# Communication_Board_Rev_A.net
KiCad netlist of a schematic drawn in EAGLE
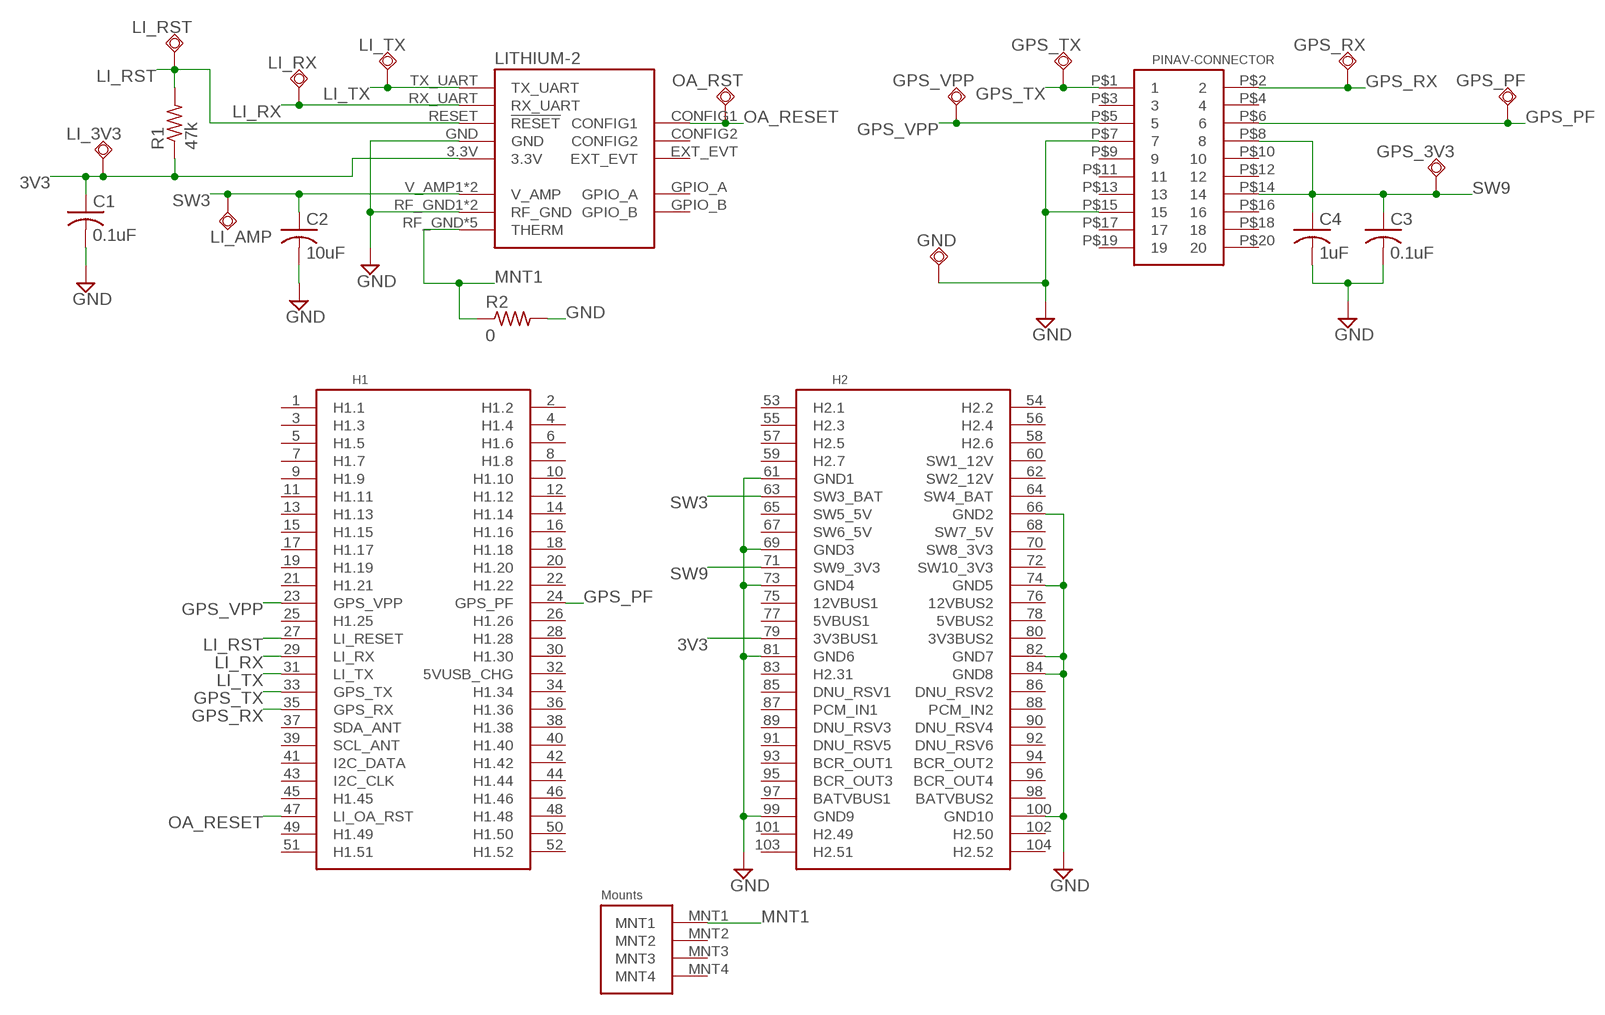
[diagram p0: schematic, sheet 1]

(export (version "E")
  (design (tool "Eeschema 10.0.6"))
  (components
    (comp (ref "C1")
      (value "0.1uF")
      (footprint "eagle-import:C0805")
      (libsource (lib "eagle-import") (part "C-USC0805"))
    )
    (comp (ref "C2")
      (value "10uF")
      (footprint "eagle-import:C0805")
      (libsource (lib "eagle-import") (part "C-USC0805"))
    )
    (comp (ref "C3")
      (value "0.1uF")
      (footprint "eagle-import:C0805")
      (libsource (lib "eagle-import") (part "C-USC0805"))
    )
    (comp (ref "C4")
      (value "1uF")
      (footprint "eagle-import:C0805")
      (libsource (lib "eagle-import") (part "C-USC0805"))
    )
    (comp (ref "GND")
      (value "TPSQTP10SQ")
      (footprint "eagle-import:TP10SQ")
      (libsource (lib "eagle-import") (part "TPSQTP10SQ"))
    )
    (comp (ref "GPS_3V3")
      (value "TPSQTP10SQ")
      (footprint "eagle-import:TP10SQ")
      (libsource (lib "eagle-import") (part "TPSQTP10SQ"))
    )
    (comp (ref "GPS_PF")
      (value "TPSQTP10SQ")
      (footprint "eagle-import:TP10SQ")
      (libsource (lib "eagle-import") (part "TPSQTP10SQ"))
    )
    (comp (ref "GPS_RX")
      (value "TPSQTP10SQ")
      (footprint "eagle-import:TP10SQ")
      (libsource (lib "eagle-import") (part "TPSQTP10SQ"))
    )
    (comp (ref "GPS_TX")
      (value "TPSQTP10SQ")
      (footprint "eagle-import:TP10SQ")
      (libsource (lib "eagle-import") (part "TPSQTP10SQ"))
    )
    (comp (ref "GPS_VPP")
      (value "TPSQTP10SQ")
      (footprint "eagle-import:TP10SQ")
      (libsource (lib "eagle-import") (part "TPSQTP10SQ"))
    )
    (comp (ref "LITHIUM-2")
      (value "LI-2")
      (footprint "eagle-import:LI-2")
      (libsource (lib "eagle-import") (part "LI-2"))
    )
    (comp (ref "LI_3V3")
      (value "TPSQTP10SQ")
      (footprint "eagle-import:TP10SQ")
      (libsource (lib "eagle-import") (part "TPSQTP10SQ"))
    )
    (comp (ref "LI_AMP")
      (value "TPSQTP10SQ")
      (footprint "eagle-import:TP10SQ")
      (libsource (lib "eagle-import") (part "TPSQTP10SQ"))
    )
    (comp (ref "LI_RST")
      (value "TPSQTP10SQ")
      (footprint "eagle-import:TP10SQ")
      (libsource (lib "eagle-import") (part "TPSQTP10SQ"))
    )
    (comp (ref "LI_RX")
      (value "TPSQTP10SQ")
      (footprint "eagle-import:TP10SQ")
      (libsource (lib "eagle-import") (part "TPSQTP10SQ"))
    )
    (comp (ref "LI_TX")
      (value "TPSQTP10SQ")
      (footprint "eagle-import:TP10SQ")
      (libsource (lib "eagle-import") (part "TPSQTP10SQ"))
    )
    (comp (ref "OA_RST")
      (value "TPSQTP10SQ")
      (footprint "eagle-import:TP10SQ")
      (libsource (lib "eagle-import") (part "TPSQTP10SQ"))
    )
    (comp (ref "PINAV-CONNECTOR")
      (value "HLE-110-02-X-DVHLE-110-X-DV-PE-BA")
      (footprint "eagle-import:HLE-110-02-X-DV-PE-BE")
      (libsource (lib "eagle-import") (part "HLE-110-02-X-DVHLE-110-X-DV-PE-BA"))
    )
    (comp (ref "R1")
      (value "47k")
      (footprint "eagle-import:R0805")
      (libsource (lib "eagle-import") (part "R-US_R0805"))
    )
    (comp (ref "R2")
      (value "0")
      (footprint "eagle-import:R0805")
      (libsource (lib "eagle-import") (part "R-US_R0805"))
    )
    (comp (ref "U$1")
      (value "PC104_NO_DIMENSION")
      (footprint "eagle-import:PC104_NO_DIMENSION")
      (libsource (lib "eagle-import") (part "PC104_NO_DIMENSION"))
    )
  )
  (nets
    (net (code "1") (name "/3V3") (class "Default")
      (node (ref "C1") (pin "1") (pinfunction "1_1") (pintype "passive"))
      (node (ref "LITHIUM-2") (pin "3.3V") (pinfunction "3.3V_3.3V") (pintype "power_in"))
      (node (ref "LI_3V3") (pin "TP") (pinfunction "TP_TP") (pintype "input"))
      (node (ref "R1") (pin "1") (pinfunction "1_1") (pintype "passive"))
      (node (ref "U$1") (pin "79") (pinfunction "3V3BUS1_79") (pintype "bidirectional"))
    )
    (net (code "2") (name "/GPS_PF") (class "Default")
      (node (ref "GPS_PF") (pin "TP") (pinfunction "TP_TP") (pintype "input"))
      (node (ref "PINAV-CONNECTOR") (pin "P$6") (pinfunction "6_P$6") (pintype "bidirectional"))
      (node (ref "U$1") (pin "24") (pinfunction "GPS_PF_24") (pintype "bidirectional"))
    )
    (net (code "3") (name "/GPS_RX") (class "Default")
      (node (ref "GPS_RX") (pin "TP") (pinfunction "TP_TP") (pintype "input"))
      (node (ref "PINAV-CONNECTOR") (pin "P$2") (pinfunction "2_P$2") (pintype "bidirectional"))
      (node (ref "U$1") (pin "35") (pinfunction "GPS_RX_35") (pintype "bidirectional"))
    )
    (net (code "4") (name "/GPS_TX") (class "Default")
      (node (ref "GPS_TX") (pin "TP") (pinfunction "TP_TP") (pintype "input"))
      (node (ref "PINAV-CONNECTOR") (pin "P$1") (pinfunction "1_P$1") (pintype "bidirectional"))
      (node (ref "U$1") (pin "33") (pinfunction "GPS_TX_33") (pintype "bidirectional"))
    )
    (net (code "5") (name "/GPS_VPP") (class "Default")
      (node (ref "GPS_VPP") (pin "TP") (pinfunction "TP_TP") (pintype "input"))
      (node (ref "PINAV-CONNECTOR") (pin "P$5") (pinfunction "5_P$5") (pintype "bidirectional"))
      (node (ref "U$1") (pin "23") (pinfunction "GPS_VPP_23") (pintype "bidirectional"))
    )
    (net (code "6") (name "/LI_RST") (class "Default")
      (node (ref "LITHIUM-2") (pin "RESET") (pinfunction "~{RESET}_RESET") (pintype "input"))
      (node (ref "LI_RST") (pin "TP") (pinfunction "TP_TP") (pintype "input"))
      (node (ref "R1") (pin "2") (pinfunction "2_2") (pintype "passive"))
      (node (ref "U$1") (pin "27") (pinfunction "LI_RESET_27") (pintype "bidirectional"))
    )
    (net (code "7") (name "/LI_RX") (class "Default")
      (node (ref "LITHIUM-2") (pin "RX_UART") (pinfunction "RX_UART_RX_UART") (pintype "input"))
      (node (ref "LI_RX") (pin "TP") (pinfunction "TP_TP") (pintype "input"))
      (node (ref "U$1") (pin "29") (pinfunction "LI_RX_29") (pintype "bidirectional"))
    )
    (net (code "8") (name "/LI_TX") (class "Default")
      (node (ref "LITHIUM-2") (pin "TX_UART") (pinfunction "TX_UART_TX_UART") (pintype "output"))
      (node (ref "LI_TX") (pin "TP") (pinfunction "TP_TP") (pintype "input"))
      (node (ref "U$1") (pin "31") (pinfunction "LI_TX_31") (pintype "bidirectional"))
    )
    (net (code "9") (name "/MNT1") (class "Default")
      (node (ref "LITHIUM-2") (pin "RF_GND") (pinfunction "THERM_RF_GND") (pintype "passive"))
      (node (ref "LITHIUM-2") (pin "THERM1") (pinfunction "THERM_THERM1") (pintype "passive"))
      (node (ref "LITHIUM-2") (pin "THERM2") (pinfunction "THERM_THERM2") (pintype "passive"))
      (node (ref "LITHIUM-2") (pin "THERM3") (pinfunction "THERM_THERM3") (pintype "passive"))
      (node (ref "LITHIUM-2") (pin "THERM4") (pinfunction "THERM_THERM4") (pintype "passive"))
      (node (ref "R2") (pin "1") (pinfunction "1_1") (pintype "passive"))
      (node (ref "U$1") (pin "MNT1") (pinfunction "MNT1_MNT1") (pintype "passive"))
    )
    (net (code "10") (name "/OA_RESET") (class "Default")
      (node (ref "LITHIUM-2") (pin "CONFIG1") (pinfunction "CONFIG1_CONFIG1") (pintype "bidirectional"))
      (node (ref "OA_RST") (pin "TP") (pinfunction "TP_TP") (pintype "input"))
      (node (ref "U$1") (pin "47") (pinfunction "LI_OA_RST_47") (pintype "bidirectional"))
    )
    (net (code "11") (name "/SW3") (class "Default")
      (node (ref "C2") (pin "1") (pinfunction "1_1") (pintype "passive"))
      (node (ref "LITHIUM-2") (pin "V_AMP1") (pinfunction "V_AMP_V_AMP1") (pintype "power_in"))
      (node (ref "LITHIUM-2") (pin "V_AMP2") (pinfunction "V_AMP_V_AMP2") (pintype "power_in"))
      (node (ref "LI_AMP") (pin "TP") (pinfunction "TP_TP") (pintype "input"))
      (node (ref "U$1") (pin "63") (pinfunction "SW3_BAT_63") (pintype "bidirectional"))
    )
    (net (code "12") (name "/SW9") (class "Default")
      (node (ref "C3") (pin "1") (pinfunction "1_1") (pintype "passive"))
      (node (ref "C4") (pin "1") (pinfunction "1_1") (pintype "passive"))
      (node (ref "GPS_3V3") (pin "TP") (pinfunction "TP_TP") (pintype "input"))
      (node (ref "PINAV-CONNECTOR") (pin "P$14") (pinfunction "14_P$14") (pintype "bidirectional"))
      (node (ref "PINAV-CONNECTOR") (pin "P$8") (pinfunction "8_P$8") (pintype "bidirectional"))
      (node (ref "U$1") (pin "71") (pinfunction "SW9_3V3_71") (pintype "bidirectional"))
    )
    (net (code "13") (name "GND") (class "Default")
      (node (ref "C1") (pin "2") (pinfunction "2_2") (pintype "passive"))
      (node (ref "C2") (pin "2") (pinfunction "2_2") (pintype "passive"))
      (node (ref "C3") (pin "2") (pinfunction "2_2") (pintype "passive"))
      (node (ref "C4") (pin "2") (pinfunction "2_2") (pintype "passive"))
      (node (ref "GND") (pin "TP") (pinfunction "TP_TP") (pintype "input"))
      (node (ref "LITHIUM-2") (pin "GND") (pinfunction "GND_GND") (pintype "power_in"))
      (node (ref "LITHIUM-2") (pin "RF_GND1") (pinfunction "RF_GND_RF_GND1") (pintype "power_in"))
      (node (ref "LITHIUM-2") (pin "RF_GND2") (pinfunction "RF_GND_RF_GND2") (pintype "power_in"))
      (node (ref "PINAV-CONNECTOR") (pin "P$15") (pinfunction "15_P$15") (pintype "bidirectional"))
      (node (ref "PINAV-CONNECTOR") (pin "P$7") (pinfunction "7_P$7") (pintype "bidirectional"))
      (node (ref "R2") (pin "2") (pinfunction "2_2") (pintype "passive"))
      (node (ref "U$1") (pin "100") (pinfunction "GND10_100") (pintype "bidirectional"))
      (node (ref "U$1") (pin "61") (pinfunction "GND1_61") (pintype "bidirectional"))
      (node (ref "U$1") (pin "66") (pinfunction "GND2_66") (pintype "bidirectional"))
      (node (ref "U$1") (pin "69") (pinfunction "GND3_69") (pintype "bidirectional"))
      (node (ref "U$1") (pin "73") (pinfunction "GND4_73") (pintype "bidirectional"))
      (node (ref "U$1") (pin "74") (pinfunction "GND5_74") (pintype "bidirectional"))
      (node (ref "U$1") (pin "81") (pinfunction "GND6_81") (pintype "bidirectional"))
      (node (ref "U$1") (pin "82") (pinfunction "GND7_82") (pintype "bidirectional"))
      (node (ref "U$1") (pin "84") (pinfunction "GND8_84") (pintype "bidirectional"))
      (node (ref "U$1") (pin "99") (pinfunction "GND9_99") (pintype "bidirectional"))
    )
    (net (code "14") (name "unconnected-(LITHIUM-2-PadCONFIG2)") (class "Default")
      (node (ref "LITHIUM-2") (pin "CONFIG2") (pinfunction "CONFIG2_CONFIG2") (pintype "bidirectional"))
    )
    (net (code "15") (name "unconnected-(LITHIUM-2-PadEXT_EVT)") (class "Default")
      (node (ref "LITHIUM-2") (pin "EXT_EVT") (pinfunction "EXT_EVT_EXT_EVT") (pintype "bidirectional"))
    )
    (net (code "16") (name "unconnected-(LITHIUM-2-PadGPIO_A)") (class "Default")
      (node (ref "LITHIUM-2") (pin "GPIO_A") (pinfunction "GPIO_A_GPIO_A") (pintype "bidirectional"))
    )
    (net (code "17") (name "unconnected-(LITHIUM-2-PadGPIO_B)") (class "Default")
      (node (ref "LITHIUM-2") (pin "GPIO_B") (pinfunction "GPIO_B_GPIO_B") (pintype "bidirectional"))
    )
    (net (code "18") (name "unconnected-(PINAV-CONNECTOR-3-PadP$3)") (class "Default")
      (node (ref "PINAV-CONNECTOR") (pin "P$3") (pinfunction "3_P$3") (pintype "bidirectional"))
    )
    (net (code "19") (name "unconnected-(PINAV-CONNECTOR-4-PadP$4)") (class "Default")
      (node (ref "PINAV-CONNECTOR") (pin "P$4") (pinfunction "4_P$4") (pintype "bidirectional"))
    )
    (net (code "20") (name "unconnected-(PINAV-CONNECTOR-9-PadP$9)") (class "Default")
      (node (ref "PINAV-CONNECTOR") (pin "P$9") (pinfunction "9_P$9") (pintype "bidirectional"))
    )
    (net (code "21") (name "unconnected-(PINAV-CONNECTOR-10-PadP$10)") (class "Default")
      (node (ref "PINAV-CONNECTOR") (pin "P$10") (pinfunction "10_P$10") (pintype "bidirectional"))
    )
    (net (code "22") (name "unconnected-(PINAV-CONNECTOR-11-PadP$11)") (class "Default")
      (node (ref "PINAV-CONNECTOR") (pin "P$11") (pinfunction "11_P$11") (pintype "bidirectional"))
    )
    (net (code "23") (name "unconnected-(PINAV-CONNECTOR-12-PadP$12)") (class "Default")
      (node (ref "PINAV-CONNECTOR") (pin "P$12") (pinfunction "12_P$12") (pintype "bidirectional"))
    )
    (net (code "24") (name "unconnected-(PINAV-CONNECTOR-13-PadP$13)") (class "Default")
      (node (ref "PINAV-CONNECTOR") (pin "P$13") (pinfunction "13_P$13") (pintype "bidirectional"))
    )
    (net (code "25") (name "unconnected-(PINAV-CONNECTOR-16-PadP$16)") (class "Default")
      (node (ref "PINAV-CONNECTOR") (pin "P$16") (pinfunction "16_P$16") (pintype "bidirectional"))
    )
    (net (code "26") (name "unconnected-(PINAV-CONNECTOR-17-PadP$17)") (class "Default")
      (node (ref "PINAV-CONNECTOR") (pin "P$17") (pinfunction "17_P$17") (pintype "bidirectional"))
    )
    (net (code "27") (name "unconnected-(PINAV-CONNECTOR-18-PadP$18)") (class "Default")
      (node (ref "PINAV-CONNECTOR") (pin "P$18") (pinfunction "18_P$18") (pintype "bidirectional"))
    )
    (net (code "28") (name "unconnected-(PINAV-CONNECTOR-19-PadP$19)") (class "Default")
      (node (ref "PINAV-CONNECTOR") (pin "P$19") (pinfunction "19_P$19") (pintype "bidirectional"))
    )
    (net (code "29") (name "unconnected-(PINAV-CONNECTOR-20-PadP$20)") (class "Default")
      (node (ref "PINAV-CONNECTOR") (pin "P$20") (pinfunction "20_P$20") (pintype "bidirectional"))
    )
    (net (code "30") (name "unconnected-(U$1-3V3BUS2-Pad80)") (class "Default")
      (node (ref "U$1") (pin "80") (pinfunction "3V3BUS2_80") (pintype "bidirectional"))
    )
    (net (code "31") (name "unconnected-(U$1-5VBUS1-Pad77)") (class "Default")
      (node (ref "U$1") (pin "77") (pinfunction "5VBUS1_77") (pintype "bidirectional"))
    )
    (net (code "32") (name "unconnected-(U$1-5VBUS2-Pad78)") (class "Default")
      (node (ref "U$1") (pin "78") (pinfunction "5VBUS2_78") (pintype "bidirectional"))
    )
    (net (code "33") (name "unconnected-(U$1-5VUSB_CHG-Pad32)") (class "Default")
      (node (ref "U$1") (pin "32") (pinfunction "5VUSB_CHG_32") (pintype "bidirectional"))
    )
    (net (code "34") (name "unconnected-(U$1-12VBUS1-Pad75)") (class "Default")
      (node (ref "U$1") (pin "75") (pinfunction "12VBUS1_75") (pintype "bidirectional"))
    )
    (net (code "35") (name "unconnected-(U$1-12VBUS2-Pad76)") (class "Default")
      (node (ref "U$1") (pin "76") (pinfunction "12VBUS2_76") (pintype "bidirectional"))
    )
    (net (code "36") (name "unconnected-(U$1-BATVBUS1-Pad97)") (class "Default")
      (node (ref "U$1") (pin "97") (pinfunction "BATVBUS1_97") (pintype "bidirectional"))
    )
    (net (code "37") (name "unconnected-(U$1-BATVBUS2-Pad98)") (class "Default")
      (node (ref "U$1") (pin "98") (pinfunction "BATVBUS2_98") (pintype "bidirectional"))
    )
    (net (code "38") (name "unconnected-(U$1-BCR_OUT1-Pad93)") (class "Default")
      (node (ref "U$1") (pin "93") (pinfunction "BCR_OUT1_93") (pintype "bidirectional"))
    )
    (net (code "39") (name "unconnected-(U$1-BCR_OUT2-Pad94)") (class "Default")
      (node (ref "U$1") (pin "94") (pinfunction "BCR_OUT2_94") (pintype "bidirectional"))
    )
    (net (code "40") (name "unconnected-(U$1-BCR_OUT3-Pad95)") (class "Default")
      (node (ref "U$1") (pin "95") (pinfunction "BCR_OUT3_95") (pintype "bidirectional"))
    )
    (net (code "41") (name "unconnected-(U$1-BCR_OUT4-Pad96)") (class "Default")
      (node (ref "U$1") (pin "96") (pinfunction "BCR_OUT4_96") (pintype "bidirectional"))
    )
    (net (code "42") (name "unconnected-(U$1-DNU_RSV1-Pad85)") (class "Default")
      (node (ref "U$1") (pin "85") (pinfunction "DNU_RSV1_85") (pintype "bidirectional"))
    )
    (net (code "43") (name "unconnected-(U$1-DNU_RSV2-Pad86)") (class "Default")
      (node (ref "U$1") (pin "86") (pinfunction "DNU_RSV2_86") (pintype "bidirectional"))
    )
    (net (code "44") (name "unconnected-(U$1-DNU_RSV3-Pad89)") (class "Default")
      (node (ref "U$1") (pin "89") (pinfunction "DNU_RSV3_89") (pintype "bidirectional"))
    )
    (net (code "45") (name "unconnected-(U$1-DNU_RSV4-Pad90)") (class "Default")
      (node (ref "U$1") (pin "90") (pinfunction "DNU_RSV4_90") (pintype "bidirectional"))
    )
    (net (code "46") (name "unconnected-(U$1-DNU_RSV5-Pad91)") (class "Default")
      (node (ref "U$1") (pin "91") (pinfunction "DNU_RSV5_91") (pintype "bidirectional"))
    )
    (net (code "47") (name "unconnected-(U$1-DNU_RSV6-Pad92)") (class "Default")
      (node (ref "U$1") (pin "92") (pinfunction "DNU_RSV6_92") (pintype "bidirectional"))
    )
    (net (code "48") (name "unconnected-(U$1-H1.1-Pad1)") (class "Default")
      (node (ref "U$1") (pin "1") (pinfunction "H1.1_1") (pintype "bidirectional"))
    )
    (net (code "49") (name "unconnected-(U$1-H1.2-Pad2)") (class "Default")
      (node (ref "U$1") (pin "2") (pinfunction "H1.2_2") (pintype "bidirectional"))
    )
    (net (code "50") (name "unconnected-(U$1-H1.3-Pad3)") (class "Default")
      (node (ref "U$1") (pin "3") (pinfunction "H1.3_3") (pintype "bidirectional"))
    )
    (net (code "51") (name "unconnected-(U$1-H1.4-Pad4)") (class "Default")
      (node (ref "U$1") (pin "4") (pinfunction "H1.4_4") (pintype "bidirectional"))
    )
    (net (code "52") (name "unconnected-(U$1-H1.5-Pad5)") (class "Default")
      (node (ref "U$1") (pin "5") (pinfunction "H1.5_5") (pintype "bidirectional"))
    )
    (net (code "53") (name "unconnected-(U$1-H1.6-Pad6)") (class "Default")
      (node (ref "U$1") (pin "6") (pinfunction "H1.6_6") (pintype "bidirectional"))
    )
    (net (code "54") (name "unconnected-(U$1-H1.7-Pad7)") (class "Default")
      (node (ref "U$1") (pin "7") (pinfunction "H1.7_7") (pintype "bidirectional"))
    )
    (net (code "55") (name "unconnected-(U$1-H1.8-Pad8)") (class "Default")
      (node (ref "U$1") (pin "8") (pinfunction "H1.8_8") (pintype "bidirectional"))
    )
    (net (code "56") (name "unconnected-(U$1-H1.9-Pad9)") (class "Default")
      (node (ref "U$1") (pin "9") (pinfunction "H1.9_9") (pintype "bidirectional"))
    )
    (net (code "57") (name "unconnected-(U$1-H1.10-Pad10)") (class "Default")
      (node (ref "U$1") (pin "10") (pinfunction "H1.10_10") (pintype "bidirectional"))
    )
    (net (code "58") (name "unconnected-(U$1-H1.11-Pad11)") (class "Default")
      (node (ref "U$1") (pin "11") (pinfunction "H1.11_11") (pintype "bidirectional"))
    )
    (net (code "59") (name "unconnected-(U$1-H1.12-Pad12)") (class "Default")
      (node (ref "U$1") (pin "12") (pinfunction "H1.12_12") (pintype "bidirectional"))
    )
    (net (code "60") (name "unconnected-(U$1-H1.13-Pad13)") (class "Default")
      (node (ref "U$1") (pin "13") (pinfunction "H1.13_13") (pintype "bidirectional"))
    )
    (net (code "61") (name "unconnected-(U$1-H1.14-Pad14)") (class "Default")
      (node (ref "U$1") (pin "14") (pinfunction "H1.14_14") (pintype "bidirectional"))
    )
    (net (code "62") (name "unconnected-(U$1-H1.15-Pad15)") (class "Default")
      (node (ref "U$1") (pin "15") (pinfunction "H1.15_15") (pintype "bidirectional"))
    )
    (net (code "63") (name "unconnected-(U$1-H1.16-Pad16)") (class "Default")
      (node (ref "U$1") (pin "16") (pinfunction "H1.16_16") (pintype "bidirectional"))
    )
    (net (code "64") (name "unconnected-(U$1-H1.17-Pad17)") (class "Default")
      (node (ref "U$1") (pin "17") (pinfunction "H1.17_17") (pintype "bidirectional"))
    )
    (net (code "65") (name "unconnected-(U$1-H1.18-Pad18)") (class "Default")
      (node (ref "U$1") (pin "18") (pinfunction "H1.18_18") (pintype "bidirectional"))
    )
    (net (code "66") (name "unconnected-(U$1-H1.19-Pad19)") (class "Default")
      (node (ref "U$1") (pin "19") (pinfunction "H1.19_19") (pintype "bidirectional"))
    )
    (net (code "67") (name "unconnected-(U$1-H1.20-Pad20)") (class "Default")
      (node (ref "U$1") (pin "20") (pinfunction "H1.20_20") (pintype "bidirectional"))
    )
    (net (code "68") (name "unconnected-(U$1-H1.21-Pad21)") (class "Default")
      (node (ref "U$1") (pin "21") (pinfunction "H1.21_21") (pintype "bidirectional"))
    )
    (net (code "69") (name "unconnected-(U$1-H1.22-Pad22)") (class "Default")
      (node (ref "U$1") (pin "22") (pinfunction "H1.22_22") (pintype "bidirectional"))
    )
    (net (code "70") (name "unconnected-(U$1-H1.25-Pad25)") (class "Default")
      (node (ref "U$1") (pin "25") (pinfunction "H1.25_25") (pintype "bidirectional"))
    )
    (net (code "71") (name "unconnected-(U$1-H1.26-Pad26)") (class "Default")
      (node (ref "U$1") (pin "26") (pinfunction "H1.26_26") (pintype "bidirectional"))
    )
    (net (code "72") (name "unconnected-(U$1-H1.28-Pad28)") (class "Default")
      (node (ref "U$1") (pin "28") (pinfunction "H1.28_28") (pintype "bidirectional"))
    )
    (net (code "73") (name "unconnected-(U$1-H1.30-Pad30)") (class "Default")
      (node (ref "U$1") (pin "30") (pinfunction "H1.30_30") (pintype "bidirectional"))
    )
    (net (code "74") (name "unconnected-(U$1-H1.34-Pad34)") (class "Default")
      (node (ref "U$1") (pin "34") (pinfunction "H1.34_34") (pintype "bidirectional"))
    )
    (net (code "75") (name "unconnected-(U$1-H1.36-Pad36)") (class "Default")
      (node (ref "U$1") (pin "36") (pinfunction "H1.36_36") (pintype "bidirectional"))
    )
    (net (code "76") (name "unconnected-(U$1-H1.38-Pad38)") (class "Default")
      (node (ref "U$1") (pin "38") (pinfunction "H1.38_38") (pintype "bidirectional"))
    )
    (net (code "77") (name "unconnected-(U$1-H1.40-Pad40)") (class "Default")
      (node (ref "U$1") (pin "40") (pinfunction "H1.40_40") (pintype "bidirectional"))
    )
    (net (code "78") (name "unconnected-(U$1-H1.42-Pad42)") (class "Default")
      (node (ref "U$1") (pin "42") (pinfunction "H1.42_42") (pintype "bidirectional"))
    )
    (net (code "79") (name "unconnected-(U$1-H1.44-Pad44)") (class "Default")
      (node (ref "U$1") (pin "44") (pinfunction "H1.44_44") (pintype "bidirectional"))
    )
    (net (code "80") (name "unconnected-(U$1-H1.45-Pad45)") (class "Default")
      (node (ref "U$1") (pin "45") (pinfunction "H1.45_45") (pintype "bidirectional"))
    )
    (net (code "81") (name "unconnected-(U$1-H1.46-Pad46)") (class "Default")
      (node (ref "U$1") (pin "46") (pinfunction "H1.46_46") (pintype "bidirectional"))
    )
    (net (code "82") (name "unconnected-(U$1-H1.48-Pad48)") (class "Default")
      (node (ref "U$1") (pin "48") (pinfunction "H1.48_48") (pintype "bidirectional"))
    )
    (net (code "83") (name "unconnected-(U$1-H1.49-Pad49)") (class "Default")
      (node (ref "U$1") (pin "49") (pinfunction "H1.49_49") (pintype "bidirectional"))
    )
    (net (code "84") (name "unconnected-(U$1-H1.50-Pad50)") (class "Default")
      (node (ref "U$1") (pin "50") (pinfunction "H1.50_50") (pintype "bidirectional"))
    )
    (net (code "85") (name "unconnected-(U$1-H1.51-Pad51)") (class "Default")
      (node (ref "U$1") (pin "51") (pinfunction "H1.51_51") (pintype "bidirectional"))
    )
    (net (code "86") (name "unconnected-(U$1-H1.52-Pad52)") (class "Default")
      (node (ref "U$1") (pin "52") (pinfunction "H1.52_52") (pintype "bidirectional"))
    )
    (net (code "87") (name "unconnected-(U$1-H2.1-Pad53)") (class "Default")
      (node (ref "U$1") (pin "53") (pinfunction "H2.1_53") (pintype "bidirectional"))
    )
    (net (code "88") (name "unconnected-(U$1-H2.2-Pad54)") (class "Default")
      (node (ref "U$1") (pin "54") (pinfunction "H2.2_54") (pintype "bidirectional"))
    )
    (net (code "89") (name "unconnected-(U$1-H2.3-Pad55)") (class "Default")
      (node (ref "U$1") (pin "55") (pinfunction "H2.3_55") (pintype "bidirectional"))
    )
    (net (code "90") (name "unconnected-(U$1-H2.4-Pad56)") (class "Default")
      (node (ref "U$1") (pin "56") (pinfunction "H2.4_56") (pintype "bidirectional"))
    )
    (net (code "91") (name "unconnected-(U$1-H2.5-Pad57)") (class "Default")
      (node (ref "U$1") (pin "57") (pinfunction "H2.5_57") (pintype "bidirectional"))
    )
    (net (code "92") (name "unconnected-(U$1-H2.6-Pad58)") (class "Default")
      (node (ref "U$1") (pin "58") (pinfunction "H2.6_58") (pintype "bidirectional"))
    )
    (net (code "93") (name "unconnected-(U$1-H2.7-Pad59)") (class "Default")
      (node (ref "U$1") (pin "59") (pinfunction "H2.7_59") (pintype "bidirectional"))
    )
    (net (code "94") (name "unconnected-(U$1-H2.31-Pad83)") (class "Default")
      (node (ref "U$1") (pin "83") (pinfunction "H2.31_83") (pintype "bidirectional"))
    )
    (net (code "95") (name "unconnected-(U$1-H2.49-Pad101)") (class "Default")
      (node (ref "U$1") (pin "101") (pinfunction "H2.49_101") (pintype "bidirectional"))
    )
    (net (code "96") (name "unconnected-(U$1-H2.50-Pad102)") (class "Default")
      (node (ref "U$1") (pin "102") (pinfunction "H2.50_102") (pintype "bidirectional"))
    )
    (net (code "97") (name "unconnected-(U$1-H2.51-Pad103)") (class "Default")
      (node (ref "U$1") (pin "103") (pinfunction "H2.51_103") (pintype "bidirectional"))
    )
    (net (code "98") (name "unconnected-(U$1-H2.52-Pad104)") (class "Default")
      (node (ref "U$1") (pin "104") (pinfunction "H2.52_104") (pintype "bidirectional"))
    )
    (net (code "99") (name "unconnected-(U$1-I2C_CLK-Pad43)") (class "Default")
      (node (ref "U$1") (pin "43") (pinfunction "I2C_CLK_43") (pintype "bidirectional"))
    )
    (net (code "100") (name "unconnected-(U$1-I2C_DATA-Pad41)") (class "Default")
      (node (ref "U$1") (pin "41") (pinfunction "I2C_DATA_41") (pintype "bidirectional"))
    )
    (net (code "101") (name "unconnected-(U$1-PCM_IN1-Pad87)") (class "Default")
      (node (ref "U$1") (pin "87") (pinfunction "PCM_IN1_87") (pintype "bidirectional"))
    )
    (net (code "102") (name "unconnected-(U$1-PCM_IN2-Pad88)") (class "Default")
      (node (ref "U$1") (pin "88") (pinfunction "PCM_IN2_88") (pintype "bidirectional"))
    )
    (net (code "103") (name "unconnected-(U$1-PadMNT2)") (class "Default")
      (node (ref "U$1") (pin "MNT2") (pinfunction "MNT2_MNT2") (pintype "passive"))
    )
    (net (code "104") (name "unconnected-(U$1-PadMNT3)") (class "Default")
      (node (ref "U$1") (pin "MNT3") (pinfunction "MNT3_MNT3") (pintype "passive"))
    )
    (net (code "105") (name "unconnected-(U$1-PadMNT4)") (class "Default")
      (node (ref "U$1") (pin "MNT4") (pinfunction "MNT4_MNT4") (pintype "passive"))
    )
    (net (code "106") (name "unconnected-(U$1-SCL_ANT-Pad39)") (class "Default")
      (node (ref "U$1") (pin "39") (pinfunction "SCL_ANT_39") (pintype "bidirectional"))
    )
    (net (code "107") (name "unconnected-(U$1-SDA_ANT-Pad37)") (class "Default")
      (node (ref "U$1") (pin "37") (pinfunction "SDA_ANT_37") (pintype "bidirectional"))
    )
    (net (code "108") (name "unconnected-(U$1-SW1_12V-Pad60)") (class "Default")
      (node (ref "U$1") (pin "60") (pinfunction "SW1_12V_60") (pintype "bidirectional"))
    )
    (net (code "109") (name "unconnected-(U$1-SW2_12V-Pad62)") (class "Default")
      (node (ref "U$1") (pin "62") (pinfunction "SW2_12V_62") (pintype "bidirectional"))
    )
    (net (code "110") (name "unconnected-(U$1-SW4_BAT-Pad64)") (class "Default")
      (node (ref "U$1") (pin "64") (pinfunction "SW4_BAT_64") (pintype "bidirectional"))
    )
    (net (code "111") (name "unconnected-(U$1-SW5_5V-Pad65)") (class "Default")
      (node (ref "U$1") (pin "65") (pinfunction "SW5_5V_65") (pintype "bidirectional"))
    )
    (net (code "112") (name "unconnected-(U$1-SW6_5V-Pad67)") (class "Default")
      (node (ref "U$1") (pin "67") (pinfunction "SW6_5V_67") (pintype "bidirectional"))
    )
    (net (code "113") (name "unconnected-(U$1-SW7_5V-Pad68)") (class "Default")
      (node (ref "U$1") (pin "68") (pinfunction "SW7_5V_68") (pintype "bidirectional"))
    )
    (net (code "114") (name "unconnected-(U$1-SW8_3V3-Pad70)") (class "Default")
      (node (ref "U$1") (pin "70") (pinfunction "SW8_3V3_70") (pintype "bidirectional"))
    )
    (net (code "115") (name "unconnected-(U$1-SW10_3V3-Pad72)") (class "Default")
      (node (ref "U$1") (pin "72") (pinfunction "SW10_3V3_72") (pintype "bidirectional"))
    )
  )
)
